# seeknobs3qtpy_30Jan2022.net
KiCad netlist of a schematic drawn in EAGLE
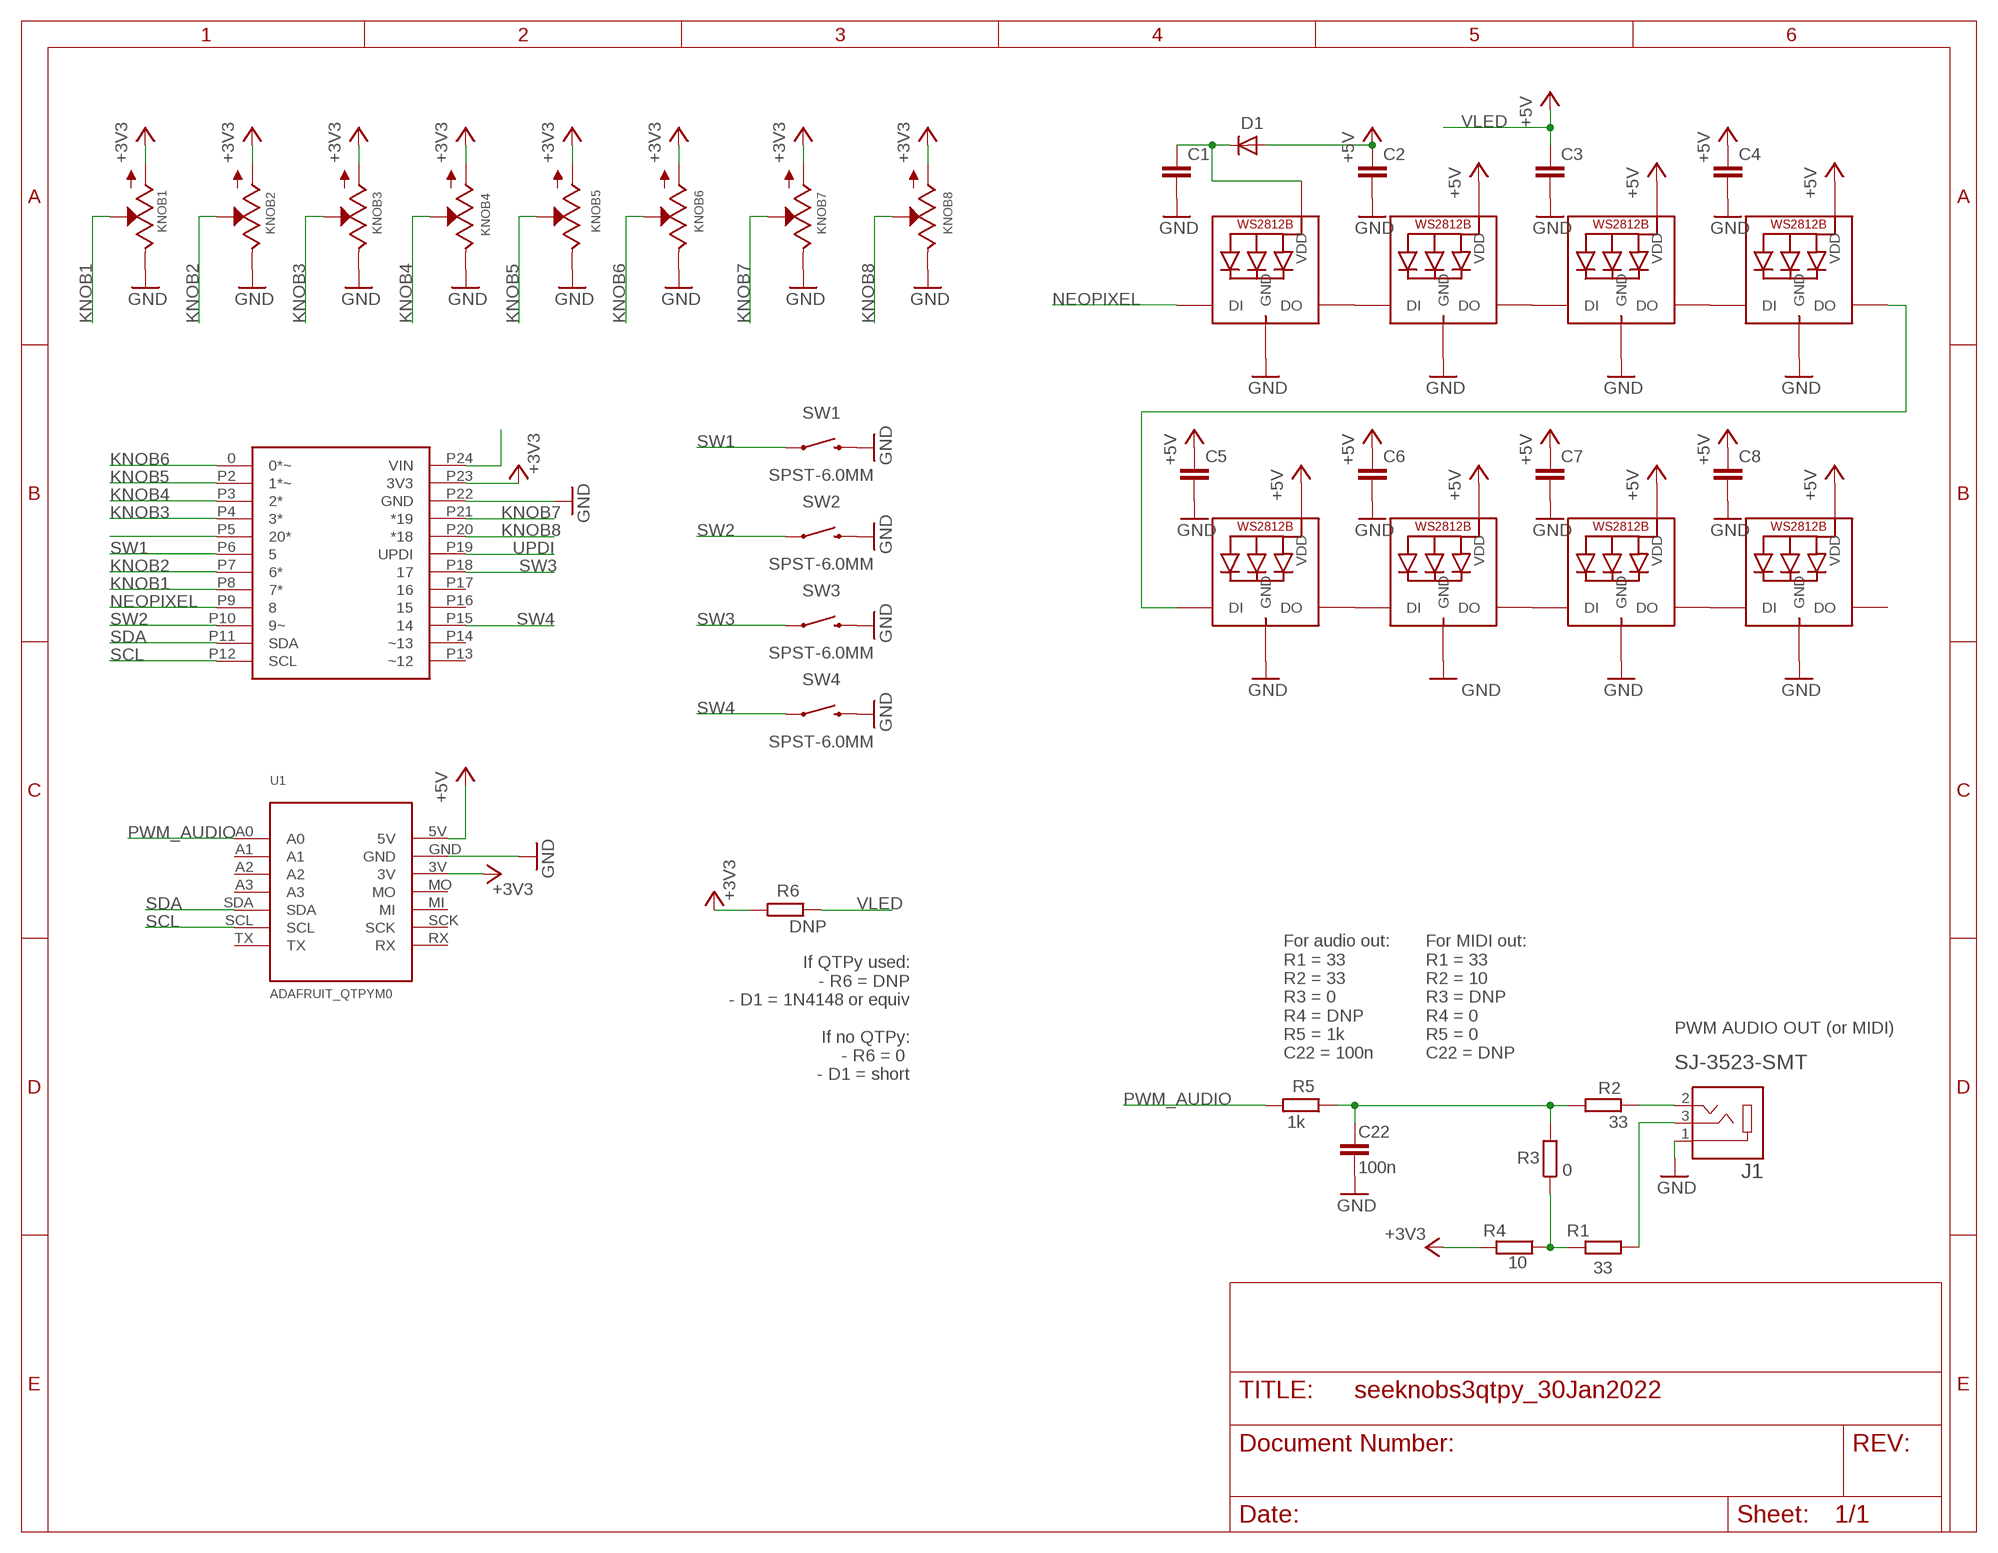
[diagram p0: schematic, sheet 1]

(export (version "E")
  (design (tool "Eeschema 10.0.6"))
  (components
    (comp (ref "C1")
      (value "C-EUC0805")
      (footprint "eagle-import:C0805")
      (libsource (lib "eagle-import") (part "C-EUC0805"))
    )
    (comp (ref "C2")
      (value "C-EUC0805")
      (footprint "eagle-import:C0805")
      (libsource (lib "eagle-import") (part "C-EUC0805"))
    )
    (comp (ref "C3")
      (value "C-EUC0805")
      (footprint "eagle-import:C0805")
      (libsource (lib "eagle-import") (part "C-EUC0805"))
    )
    (comp (ref "C4")
      (value "C-EUC0805")
      (footprint "eagle-import:C0805")
      (libsource (lib "eagle-import") (part "C-EUC0805"))
    )
    (comp (ref "C5")
      (value "C-EUC0805")
      (footprint "eagle-import:C0805")
      (libsource (lib "eagle-import") (part "C-EUC0805"))
    )
    (comp (ref "C6")
      (value "C-EUC0805")
      (footprint "eagle-import:C0805")
      (libsource (lib "eagle-import") (part "C-EUC0805"))
    )
    (comp (ref "C7")
      (value "C-EUC0805")
      (footprint "eagle-import:C0805")
      (libsource (lib "eagle-import") (part "C-EUC0805"))
    )
    (comp (ref "C8")
      (value "C-EUC0805")
      (footprint "eagle-import:C0805")
      (libsource (lib "eagle-import") (part "C-EUC0805"))
    )
    (comp (ref "C22")
      (value "100n")
      (footprint "eagle-import:C0805")
      (libsource (lib "eagle-import") (part "C-EUC0805"))
    )
    (comp (ref "D1")
      (value "DIODESOD-123")
      (footprint "eagle-import:SOD-123")
      (libsource (lib "eagle-import") (part "DIODESOD-123"))
    )
    (comp (ref "J1")
      (value "SJ-3523-SMT")
      (footprint "eagle-import:CUI_SJ-3523-SMT")
      (fields
        (field (name "DIGI-KEY_PART_NUMBER") "CP-3523SJCT-ND")
        (field (name "MF") "CUI Devices")
        (field (name "MP") "SJ-3523-SMT-TR")
      )
      (libsource (lib "eagle-import") (part "SJ-3523-SMT"))
    )
    (comp (ref "KNOB1")
      (value "POT")
      (footprint "eagle-import:ALPS_POT")
      (libsource (lib "eagle-import") (part "POT"))
    )
    (comp (ref "KNOB2")
      (value "POT")
      (footprint "eagle-import:ALPS_POT")
      (libsource (lib "eagle-import") (part "POT"))
    )
    (comp (ref "KNOB3")
      (value "POT")
      (footprint "eagle-import:ALPS_POT")
      (libsource (lib "eagle-import") (part "POT"))
    )
    (comp (ref "KNOB4")
      (value "POT")
      (footprint "eagle-import:ALPS_POT")
      (libsource (lib "eagle-import") (part "POT"))
    )
    (comp (ref "KNOB5")
      (value "POT")
      (footprint "eagle-import:ALPS_POT")
      (libsource (lib "eagle-import") (part "POT"))
    )
    (comp (ref "KNOB6")
      (value "POT")
      (footprint "eagle-import:ALPS_POT")
      (libsource (lib "eagle-import") (part "POT"))
    )
    (comp (ref "KNOB7")
      (value "POT")
      (footprint "eagle-import:ALPS_POT")
      (libsource (lib "eagle-import") (part "POT"))
    )
    (comp (ref "KNOB8")
      (value "POT")
      (footprint "eagle-import:ALPS_POT")
      (libsource (lib "eagle-import") (part "POT"))
    )
    (comp (ref "LED1")
      (value "MICROBUILDER_WS2812B5050")
      (footprint "eagle-import:MICROBUILDER_WS2812B")
      (libsource (lib "eagle-import") (part "MICROBUILDER_WS2812B5050"))
    )
    (comp (ref "LED2")
      (value "MICROBUILDER_WS2812B5050")
      (footprint "eagle-import:MICROBUILDER_WS2812B")
      (libsource (lib "eagle-import") (part "MICROBUILDER_WS2812B5050"))
    )
    (comp (ref "LED3")
      (value "MICROBUILDER_WS2812B5050")
      (footprint "eagle-import:MICROBUILDER_WS2812B")
      (libsource (lib "eagle-import") (part "MICROBUILDER_WS2812B5050"))
    )
    (comp (ref "LED4")
      (value "MICROBUILDER_WS2812B5050")
      (footprint "eagle-import:MICROBUILDER_WS2812B")
      (libsource (lib "eagle-import") (part "MICROBUILDER_WS2812B5050"))
    )
    (comp (ref "LED5")
      (value "MICROBUILDER_WS2812B5050")
      (footprint "eagle-import:MICROBUILDER_WS2812B")
      (libsource (lib "eagle-import") (part "MICROBUILDER_WS2812B5050"))
    )
    (comp (ref "LED6")
      (value "MICROBUILDER_WS2812B5050")
      (footprint "eagle-import:MICROBUILDER_WS2812B")
      (libsource (lib "eagle-import") (part "MICROBUILDER_WS2812B5050"))
    )
    (comp (ref "LED7")
      (value "MICROBUILDER_WS2812B5050")
      (footprint "eagle-import:MICROBUILDER_WS2812B")
      (libsource (lib "eagle-import") (part "MICROBUILDER_WS2812B5050"))
    )
    (comp (ref "LED8")
      (value "MICROBUILDER_WS2812B5050")
      (footprint "eagle-import:MICROBUILDER_WS2812B")
      (libsource (lib "eagle-import") (part "MICROBUILDER_WS2812B5050"))
    )
    (comp (ref "R1")
      (value "33")
      (footprint "eagle-import:R0805")
      (libsource (lib "eagle-import") (part "R-EU_R0805"))
    )
    (comp (ref "R2")
      (value "33")
      (footprint "eagle-import:R0805")
      (libsource (lib "eagle-import") (part "R-EU_R0805"))
    )
    (comp (ref "R3")
      (value "0")
      (footprint "eagle-import:R0805")
      (libsource (lib "eagle-import") (part "R-EU_R0805"))
    )
    (comp (ref "R4")
      (value "10")
      (footprint "eagle-import:R0805")
      (libsource (lib "eagle-import") (part "R-EU_R0805"))
    )
    (comp (ref "R5")
      (value "1k")
      (footprint "eagle-import:R0805")
      (libsource (lib "eagle-import") (part "R-EU_R0805"))
    )
    (comp (ref "R6")
      (value "DNP")
      (footprint "eagle-import:R0805")
      (libsource (lib "eagle-import") (part "R-EU_R0805"))
    )
    (comp (ref "SEESAW")
      (value "ADAFRUIT_SEESAW_ATTINY817")
      (footprint "eagle-import:ADAFRUIT_SEESAW_ATTINY817")
      (libsource (lib "eagle-import") (part "ADAFRUIT_SEESAW_ATTINY817"))
    )
    (comp (ref "SW1")
      (value "SPST-6.0MM")
      (footprint "eagle-import:TACTILE_SWITCH_PTH_6.0MM")
      (libsource (lib "eagle-import") (part "MOMENTARY-SWITCH-SPST-PTH-6.0MM"))
    )
    (comp (ref "SW2")
      (value "SPST-6.0MM")
      (footprint "eagle-import:TACTILE_SWITCH_PTH_6.0MM")
      (libsource (lib "eagle-import") (part "MOMENTARY-SWITCH-SPST-PTH-6.0MM"))
    )
    (comp (ref "SW3")
      (value "SPST-6.0MM")
      (footprint "eagle-import:TACTILE_SWITCH_PTH_6.0MM")
      (libsource (lib "eagle-import") (part "MOMENTARY-SWITCH-SPST-PTH-6.0MM"))
    )
    (comp (ref "SW4")
      (value "SPST-6.0MM")
      (footprint "eagle-import:TACTILE_SWITCH_PTH_6.0MM")
      (libsource (lib "eagle-import") (part "MOMENTARY-SWITCH-SPST-PTH-6.0MM"))
    )
    (comp (ref "U1")
      (value "ADAFRUIT_QTPYM0")
      (footprint "eagle-import:ADAFRUIT_QTPY_M0")
      (libsource (lib "eagle-import") (part "ADAFRUIT_QTPYM0"))
    )
  )
  (nets
    (net (code "1") (name "+3V3") (class "Default")
      (node (ref "KNOB1") (pin "P$3") (pinfunction "A_P$3") (pintype "passive"))
      (node (ref "KNOB2") (pin "P$3") (pinfunction "A_P$3") (pintype "passive"))
      (node (ref "KNOB3") (pin "P$3") (pinfunction "A_P$3") (pintype "passive"))
      (node (ref "KNOB4") (pin "P$3") (pinfunction "A_P$3") (pintype "passive"))
      (node (ref "KNOB5") (pin "P$3") (pinfunction "A_P$3") (pintype "passive"))
      (node (ref "KNOB6") (pin "P$3") (pinfunction "A_P$3") (pintype "passive"))
      (node (ref "KNOB7") (pin "P$3") (pinfunction "A_P$3") (pintype "passive"))
      (node (ref "KNOB8") (pin "P$3") (pinfunction "A_P$3") (pintype "passive"))
      (node (ref "R4") (pin "2") (pinfunction "2_2") (pintype "passive"))
      (node (ref "R6") (pin "2") (pinfunction "2_2") (pintype "passive"))
      (node (ref "SEESAW") (pin "P23") (pinfunction "3V3_P23") (pintype "bidirectional"))
      (node (ref "U1") (pin "3V") (pinfunction "3V_3V") (pintype "bidirectional"))
    )
    (net (code "2") (name "+5V") (class "Default")
      (node (ref "C2") (pin "1") (pinfunction "1_1") (pintype "passive"))
      (node (ref "C3") (pin "1") (pinfunction "1_1") (pintype "passive"))
      (node (ref "C4") (pin "1") (pinfunction "1_1") (pintype "passive"))
      (node (ref "C5") (pin "1") (pinfunction "1_1") (pintype "passive"))
      (node (ref "C6") (pin "1") (pinfunction "1_1") (pintype "passive"))
      (node (ref "C7") (pin "1") (pinfunction "1_1") (pintype "passive"))
      (node (ref "C8") (pin "1") (pinfunction "1_1") (pintype "passive"))
      (node (ref "D1") (pin "A") (pinfunction "A_A") (pintype "passive"))
      (node (ref "LED2") (pin "1-VDD") (pinfunction "VDD_1-VDD") (pintype "power_in"))
      (node (ref "LED3") (pin "1-VDD") (pinfunction "VDD_1-VDD") (pintype "power_in"))
      (node (ref "LED4") (pin "1-VDD") (pinfunction "VDD_1-VDD") (pintype "power_in"))
      (node (ref "LED5") (pin "1-VDD") (pinfunction "VDD_1-VDD") (pintype "power_in"))
      (node (ref "LED6") (pin "1-VDD") (pinfunction "VDD_1-VDD") (pintype "power_in"))
      (node (ref "LED7") (pin "1-VDD") (pinfunction "VDD_1-VDD") (pintype "power_in"))
      (node (ref "LED8") (pin "1-VDD") (pinfunction "VDD_1-VDD") (pintype "power_in"))
      (node (ref "R6") (pin "1") (pinfunction "1_1") (pintype "passive"))
      (node (ref "U1") (pin "5V") (pinfunction "5V_5V") (pintype "bidirectional"))
    )
    (net (code "3") (name "/KNOB1") (class "Default")
      (node (ref "KNOB1") (pin "P$2") (pinfunction "S_P$2") (pintype "passive"))
      (node (ref "SEESAW") (pin "P8") (pinfunction "7*_P8") (pintype "bidirectional"))
    )
    (net (code "4") (name "/KNOB2") (class "Default")
      (node (ref "KNOB2") (pin "P$2") (pinfunction "S_P$2") (pintype "passive"))
      (node (ref "SEESAW") (pin "P7") (pinfunction "6*_P7") (pintype "bidirectional"))
    )
    (net (code "5") (name "/KNOB3") (class "Default")
      (node (ref "KNOB3") (pin "P$2") (pinfunction "S_P$2") (pintype "passive"))
      (node (ref "SEESAW") (pin "P4") (pinfunction "3*_P4") (pintype "bidirectional"))
    )
    (net (code "6") (name "/KNOB4") (class "Default")
      (node (ref "KNOB4") (pin "P$2") (pinfunction "S_P$2") (pintype "passive"))
      (node (ref "SEESAW") (pin "P3") (pinfunction "2*_P3") (pintype "bidirectional"))
    )
    (net (code "7") (name "/KNOB5") (class "Default")
      (node (ref "KNOB5") (pin "P$2") (pinfunction "S_P$2") (pintype "passive"))
      (node (ref "SEESAW") (pin "P2") (pinfunction "1*~{}_P2") (pintype "bidirectional"))
    )
    (net (code "8") (name "/KNOB6") (class "Default")
      (node (ref "KNOB6") (pin "P$2") (pinfunction "S_P$2") (pintype "passive"))
      (node (ref "SEESAW") (pin "0") (pinfunction "0*~{}_0") (pintype "bidirectional"))
    )
    (net (code "9") (name "/KNOB7") (class "Default")
      (node (ref "KNOB7") (pin "P$2") (pinfunction "S_P$2") (pintype "passive"))
      (node (ref "SEESAW") (pin "P21") (pinfunction "*19_P21") (pintype "bidirectional"))
    )
    (net (code "10") (name "/KNOB8") (class "Default")
      (node (ref "KNOB8") (pin "P$2") (pinfunction "S_P$2") (pintype "passive"))
      (node (ref "SEESAW") (pin "P20") (pinfunction "*18_P20") (pintype "bidirectional"))
    )
    (net (code "11") (name "/NEOPIXEL") (class "Default")
      (node (ref "LED1") (pin "4-DIN") (pinfunction "DI_4-DIN") (pintype "input"))
      (node (ref "SEESAW") (pin "P9") (pinfunction "8_P9") (pintype "bidirectional"))
    )
    (net (code "12") (name "/PWM_AUDIO") (class "Default")
      (node (ref "R5") (pin "2") (pinfunction "2_2") (pintype "passive"))
      (node (ref "U1") (pin "A0") (pinfunction "A0_A0") (pintype "bidirectional"))
    )
    (net (code "13") (name "/SCL") (class "Default")
      (node (ref "SEESAW") (pin "P12") (pinfunction "SCL_P12") (pintype "bidirectional"))
      (node (ref "U1") (pin "SCL") (pinfunction "SCL_SCL") (pintype "bidirectional"))
    )
    (net (code "14") (name "/SDA") (class "Default")
      (node (ref "SEESAW") (pin "P11") (pinfunction "SDA_P11") (pintype "bidirectional"))
      (node (ref "U1") (pin "SDA") (pinfunction "SDA_SDA") (pintype "bidirectional"))
    )
    (net (code "15") (name "/SW1") (class "Default")
      (node (ref "SEESAW") (pin "P6") (pinfunction "5_P6") (pintype "bidirectional"))
      (node (ref "SW1") (pin "1") (pinfunction "1_1") (pintype "passive"))
    )
    (net (code "16") (name "/SW2") (class "Default")
      (node (ref "SEESAW") (pin "P10") (pinfunction "9~{}_P10") (pintype "bidirectional"))
      (node (ref "SW2") (pin "1") (pinfunction "1_1") (pintype "passive"))
    )
    (net (code "17") (name "/SW3") (class "Default")
      (node (ref "SEESAW") (pin "P18") (pinfunction "17_P18") (pintype "bidirectional"))
      (node (ref "SW3") (pin "1") (pinfunction "1_1") (pintype "passive"))
    )
    (net (code "18") (name "/SW4") (class "Default")
      (node (ref "SEESAW") (pin "P15") (pinfunction "14_P15") (pintype "bidirectional"))
      (node (ref "SW4") (pin "1") (pinfunction "1_1") (pintype "passive"))
    )
    (net (code "19") (name "/UPDI") (class "Default")
      (node (ref "SEESAW") (pin "P19") (pinfunction "UPDI_P19") (pintype "bidirectional"))
    )
    (net (code "20") (name "GND") (class "Default")
      (node (ref "C1") (pin "2") (pinfunction "2_2") (pintype "passive"))
      (node (ref "C2") (pin "2") (pinfunction "2_2") (pintype "passive"))
      (node (ref "C22") (pin "2") (pinfunction "2_2") (pintype "passive"))
      (node (ref "C3") (pin "2") (pinfunction "2_2") (pintype "passive"))
      (node (ref "C4") (pin "2") (pinfunction "2_2") (pintype "passive"))
      (node (ref "C5") (pin "2") (pinfunction "2_2") (pintype "passive"))
      (node (ref "C6") (pin "2") (pinfunction "2_2") (pintype "passive"))
      (node (ref "C7") (pin "2") (pinfunction "2_2") (pintype "passive"))
      (node (ref "C8") (pin "2") (pinfunction "2_2") (pintype "passive"))
      (node (ref "J1") (pin "1") (pinfunction "1_1") (pintype "passive"))
      (node (ref "KNOB1") (pin "P$1") (pinfunction "E_P$1") (pintype "passive"))
      (node (ref "KNOB2") (pin "P$1") (pinfunction "E_P$1") (pintype "passive"))
      (node (ref "KNOB3") (pin "P$1") (pinfunction "E_P$1") (pintype "passive"))
      (node (ref "KNOB4") (pin "P$1") (pinfunction "E_P$1") (pintype "passive"))
      (node (ref "KNOB5") (pin "P$1") (pinfunction "E_P$1") (pintype "passive"))
      (node (ref "KNOB6") (pin "P$1") (pinfunction "E_P$1") (pintype "passive"))
      (node (ref "KNOB7") (pin "P$1") (pinfunction "E_P$1") (pintype "passive"))
      (node (ref "KNOB8") (pin "P$1") (pinfunction "E_P$1") (pintype "passive"))
      (node (ref "LED1") (pin "3-GND") (pinfunction "GND_3-GND") (pintype "power_in"))
      (node (ref "LED2") (pin "3-GND") (pinfunction "GND_3-GND") (pintype "power_in"))
      (node (ref "LED3") (pin "3-GND") (pinfunction "GND_3-GND") (pintype "power_in"))
      (node (ref "LED4") (pin "3-GND") (pinfunction "GND_3-GND") (pintype "power_in"))
      (node (ref "LED5") (pin "3-GND") (pinfunction "GND_3-GND") (pintype "power_in"))
      (node (ref "LED6") (pin "3-GND") (pinfunction "GND_3-GND") (pintype "power_in"))
      (node (ref "LED7") (pin "3-GND") (pinfunction "GND_3-GND") (pintype "power_in"))
      (node (ref "LED8") (pin "3-GND") (pinfunction "GND_3-GND") (pintype "power_in"))
      (node (ref "SEESAW") (pin "P22") (pinfunction "GND_P22") (pintype "bidirectional"))
      (node (ref "SW1") (pin "3") (pinfunction "2_3") (pintype "passive"))
      (node (ref "SW2") (pin "3") (pinfunction "2_3") (pintype "passive"))
      (node (ref "SW3") (pin "3") (pinfunction "2_3") (pintype "passive"))
      (node (ref "SW4") (pin "3") (pinfunction "2_3") (pintype "passive"))
      (node (ref "U1") (pin "GND") (pinfunction "GND_GND") (pintype "bidirectional"))
    )
    (net (code "21") (name "Net-(C22-Pad1)") (class "Default")
      (node (ref "C22") (pin "1") (pinfunction "1_1") (pintype "passive"))
      (node (ref "R2") (pin "2") (pinfunction "2_2") (pintype "passive"))
      (node (ref "R3") (pin "2") (pinfunction "2_2") (pintype "passive"))
      (node (ref "R5") (pin "1") (pinfunction "1_1") (pintype "passive"))
    )
    (net (code "22") (name "Net-(J1-Pad2)") (class "Default")
      (node (ref "J1") (pin "2") (pinfunction "2_2") (pintype "passive"))
      (node (ref "R2") (pin "1") (pinfunction "1_1") (pintype "passive"))
    )
    (net (code "23") (name "Net-(J1-Pad3)") (class "Default")
      (node (ref "J1") (pin "3") (pinfunction "3_3") (pintype "passive"))
      (node (ref "R1") (pin "1") (pinfunction "1_1") (pintype "passive"))
    )
    (net (code "24") (name "Net-(LED1-DO)") (class "Default")
      (node (ref "LED1") (pin "2-DOUT") (pinfunction "DO_2-DOUT") (pintype "output"))
      (node (ref "LED2") (pin "4-DIN") (pinfunction "DI_4-DIN") (pintype "input"))
    )
    (net (code "25") (name "Net-(LED1-VDD)") (class "Default")
      (node (ref "C1") (pin "1") (pinfunction "1_1") (pintype "passive"))
      (node (ref "D1") (pin "C") (pinfunction "C_C") (pintype "passive"))
      (node (ref "LED1") (pin "1-VDD") (pinfunction "VDD_1-VDD") (pintype "power_in"))
    )
    (net (code "26") (name "Net-(LED2-DO)") (class "Default")
      (node (ref "LED2") (pin "2-DOUT") (pinfunction "DO_2-DOUT") (pintype "output"))
      (node (ref "LED3") (pin "4-DIN") (pinfunction "DI_4-DIN") (pintype "input"))
    )
    (net (code "27") (name "Net-(LED3-DO)") (class "Default")
      (node (ref "LED3") (pin "2-DOUT") (pinfunction "DO_2-DOUT") (pintype "output"))
      (node (ref "LED4") (pin "4-DIN") (pinfunction "DI_4-DIN") (pintype "input"))
    )
    (net (code "28") (name "Net-(LED4-DO)") (class "Default")
      (node (ref "LED4") (pin "2-DOUT") (pinfunction "DO_2-DOUT") (pintype "output"))
      (node (ref "LED5") (pin "4-DIN") (pinfunction "DI_4-DIN") (pintype "input"))
    )
    (net (code "29") (name "Net-(LED5-DO)") (class "Default")
      (node (ref "LED5") (pin "2-DOUT") (pinfunction "DO_2-DOUT") (pintype "output"))
      (node (ref "LED6") (pin "4-DIN") (pinfunction "DI_4-DIN") (pintype "input"))
    )
    (net (code "30") (name "Net-(LED6-DO)") (class "Default")
      (node (ref "LED6") (pin "2-DOUT") (pinfunction "DO_2-DOUT") (pintype "output"))
      (node (ref "LED7") (pin "4-DIN") (pinfunction "DI_4-DIN") (pintype "input"))
    )
    (net (code "31") (name "Net-(LED7-DO)") (class "Default")
      (node (ref "LED7") (pin "2-DOUT") (pinfunction "DO_2-DOUT") (pintype "output"))
      (node (ref "LED8") (pin "4-DIN") (pinfunction "DI_4-DIN") (pintype "input"))
    )
    (net (code "32") (name "Net-(R1-Pad2)") (class "Default")
      (node (ref "R1") (pin "2") (pinfunction "2_2") (pintype "passive"))
      (node (ref "R3") (pin "1") (pinfunction "1_1") (pintype "passive"))
      (node (ref "R4") (pin "1") (pinfunction "1_1") (pintype "passive"))
    )
    (net (code "33") (name "unconnected-(LED8-DO-Pad2-DOUT)") (class "Default")
      (node (ref "LED8") (pin "2-DOUT") (pinfunction "DO_2-DOUT") (pintype "output"))
    )
    (net (code "34") (name "unconnected-(SEESAW-15-PadP16)") (class "Default")
      (node (ref "SEESAW") (pin "P16") (pinfunction "15_P16") (pintype "bidirectional"))
    )
    (net (code "35") (name "unconnected-(SEESAW-16-PadP17)") (class "Default")
      (node (ref "SEESAW") (pin "P17") (pinfunction "16_P17") (pintype "bidirectional"))
    )
    (net (code "36") (name "unconnected-(SEESAW-20*-PadP5)") (class "Default")
      (node (ref "SEESAW") (pin "P5") (pinfunction "20*_P5") (pintype "bidirectional"))
    )
    (net (code "37") (name "unconnected-(SEESAW-VIN-PadP24)") (class "Default")
      (node (ref "SEESAW") (pin "P24") (pinfunction "VIN_P24") (pintype "bidirectional"))
    )
    (net (code "38") (name "unconnected-(SEESAW-~{12}-PadP13)") (class "Default")
      (node (ref "SEESAW") (pin "P13") (pinfunction "~{12}_P13") (pintype "bidirectional"))
    )
    (net (code "39") (name "unconnected-(SEESAW-~{13}-PadP14)") (class "Default")
      (node (ref "SEESAW") (pin "P14") (pinfunction "~{13}_P14") (pintype "bidirectional"))
    )
    (net (code "40") (name "unconnected-(U1-PadA1)") (class "Default")
      (node (ref "U1") (pin "A1") (pinfunction "A1_A1") (pintype "bidirectional"))
    )
    (net (code "41") (name "unconnected-(U1-PadA2)") (class "Default")
      (node (ref "U1") (pin "A2") (pinfunction "A2_A2") (pintype "bidirectional"))
    )
    (net (code "42") (name "unconnected-(U1-PadA3)") (class "Default")
      (node (ref "U1") (pin "A3") (pinfunction "A3_A3") (pintype "bidirectional"))
    )
    (net (code "43") (name "unconnected-(U1-PadMI)") (class "Default")
      (node (ref "U1") (pin "MI") (pinfunction "MI_MI") (pintype "bidirectional"))
    )
    (net (code "44") (name "unconnected-(U1-PadMO)") (class "Default")
      (node (ref "U1") (pin "MO") (pinfunction "MO_MO") (pintype "bidirectional"))
    )
    (net (code "45") (name "unconnected-(U1-PadRX)") (class "Default")
      (node (ref "U1") (pin "RX") (pinfunction "RX_RX") (pintype "bidirectional"))
    )
    (net (code "46") (name "unconnected-(U1-PadSCK)") (class "Default")
      (node (ref "U1") (pin "SCK") (pinfunction "SCK_SCK") (pintype "bidirectional"))
    )
    (net (code "47") (name "unconnected-(U1-PadTX)") (class "Default")
      (node (ref "U1") (pin "TX") (pinfunction "TX_TX") (pintype "bidirectional"))
    )
  )
)
